# PCBmoteurs.net
KiCad netlist of a schematic drawn in EAGLE
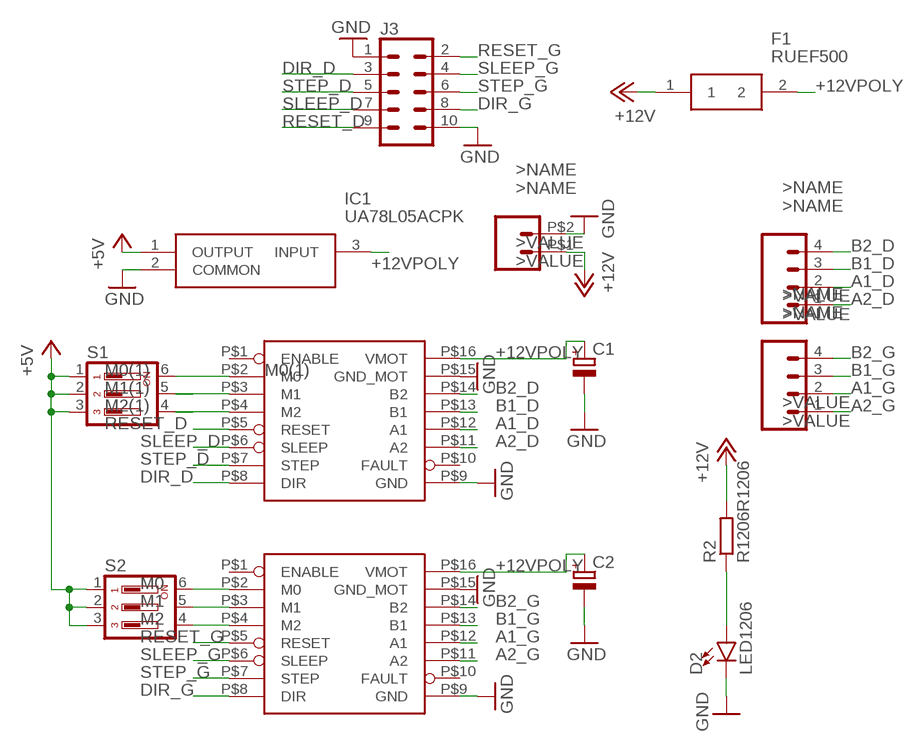
[diagram p0: schematic, sheet 1]

(export (version "E")
  (design (tool "Eeschema 10.0.6"))
  (components
    (comp (ref "C1")
      (value "CPOL-EUE3.5-8")
      (footprint "eagle-import:E3,5-8")
      (libsource (lib "eagle-import") (part "CPOL-EUE3.5-8"))
    )
    (comp (ref "C2")
      (value "CPOL-EUE3.5-8")
      (footprint "eagle-import:E3,5-8")
      (libsource (lib "eagle-import") (part "CPOL-EUE3.5-8"))
    )
    (comp (ref "D2")
      (value "LED1206")
      (footprint "eagle-import:1206")
      (libsource (lib "eagle-import") (part "LED1206"))
    )
    (comp (ref "F1")
      (value "RUEF500")
      (footprint "eagle-import:RUEF500")
      (fields (field (name "RS_PART_NUMBER") "5176843"))
      (libsource (lib "eagle-import") (part "RUEF500"))
    )
    (comp (ref "IC1")
      (value "UA78L05ACPK")
      (footprint "eagle-import:PK(R-PSSO-F3)")
      (fields (field (name "MOUSER_PART_NUMBER") "595-UA78L05ACPK"))
      (libsource (lib "eagle-import") (part "UA78L05ACPK"))
    )
    (comp (ref "J2")
      (value "CONN_027A-C")
      (footprint "eagle-import:NSK396-2C")
      (libsource (lib "eagle-import") (part "CONN_027A-C"))
    )
    (comp (ref "J3")
      (value "CONN_05X2SHD")
      (footprint "eagle-import:2X5-SHROUDED")
      (libsource (lib "eagle-import") (part "CONN_05X2SHD"))
    )
    (comp (ref "J4")
      (value "CONN_04POLAR")
      (footprint "eagle-import:MOLEX-1X4")
      (libsource (lib "eagle-import") (part "CONN_04POLAR"))
    )
    (comp (ref "J6")
      (value "CONN_04POLAR")
      (footprint "eagle-import:MOLEX-1X4")
      (libsource (lib "eagle-import") (part "CONN_04POLAR"))
    )
    (comp (ref "R2")
      (value "R1206R1206")
      (footprint "eagle-import:R1206")
      (libsource (lib "eagle-import") (part "R1206R1206"))
    )
    (comp (ref "S1")
      (value "DS03")
      (footprint "eagle-import:DS-03")
      (libsource (lib "eagle-import") (part "DS03"))
    )
    (comp (ref "S2")
      (value "DS03")
      (footprint "eagle-import:DS-03")
      (libsource (lib "eagle-import") (part "DS03"))
    )
    (comp (ref "U$1")
      (value "DRV8825")
      (footprint "eagle-import:DRIVER_CARRIER_POLOLU_16")
      (libsource (lib "eagle-import") (part "DRV8825"))
    )
    (comp (ref "U$2")
      (value "DRV8825")
      (footprint "eagle-import:DRIVER_CARRIER_POLOLU_16")
      (libsource (lib "eagle-import") (part "DRV8825"))
    )
  )
  (nets
    (net (code "1") (name "+5V") (class "Default")
      (node (ref "IC1") (pin "1") (pinfunction "OUTPUT_1") (pintype "bidirectional"))
      (node (ref "S1") (pin "1") (pinfunction "1_1") (pintype "passive"))
      (node (ref "S1") (pin "2") (pinfunction "2_2") (pintype "passive"))
      (node (ref "S1") (pin "3") (pinfunction "3_3") (pintype "passive"))
      (node (ref "S2") (pin "1") (pinfunction "1_1") (pintype "passive"))
      (node (ref "S2") (pin "2") (pinfunction "2_2") (pintype "passive"))
      (node (ref "S2") (pin "3") (pinfunction "3_3") (pintype "passive"))
    )
    (net (code "2") (name "+12V") (class "Default")
      (node (ref "F1") (pin "1") (pinfunction "1_1") (pintype "bidirectional"))
      (node (ref "J2") (pin "P$1") (pinfunction "1_P$1") (pintype "passive"))
      (node (ref "R2") (pin "2") (pinfunction "2_2") (pintype "passive"))
    )
    (net (code "3") (name "/+12VPOLY") (class "Default")
      (node (ref "C1") (pin "+") (pinfunction "+_+") (pintype "passive"))
      (node (ref "C2") (pin "+") (pinfunction "+_+") (pintype "passive"))
      (node (ref "F1") (pin "2") (pinfunction "2_2") (pintype "bidirectional"))
      (node (ref "IC1") (pin "3") (pinfunction "INPUT_3") (pintype "bidirectional"))
      (node (ref "U$1") (pin "P$16") (pinfunction "VMOT_P$16") (pintype "bidirectional"))
      (node (ref "U$2") (pin "P$16") (pinfunction "VMOT_P$16") (pintype "bidirectional"))
    )
    (net (code "4") (name "/A1_D") (class "Default")
      (node (ref "J4") (pin "2") (pinfunction "2_2") (pintype "passive"))
      (node (ref "U$1") (pin "P$12") (pinfunction "A1_P$12") (pintype "bidirectional"))
    )
    (net (code "5") (name "/A1_G") (class "Default")
      (node (ref "J6") (pin "2") (pinfunction "2_2") (pintype "passive"))
      (node (ref "U$2") (pin "P$12") (pinfunction "A1_P$12") (pintype "bidirectional"))
    )
    (net (code "6") (name "/A2_D") (class "Default")
      (node (ref "J4") (pin "1") (pinfunction "1_1") (pintype "passive"))
      (node (ref "U$1") (pin "P$11") (pinfunction "A2_P$11") (pintype "bidirectional"))
    )
    (net (code "7") (name "/A2_G") (class "Default")
      (node (ref "J6") (pin "1") (pinfunction "1_1") (pintype "passive"))
      (node (ref "U$2") (pin "P$11") (pinfunction "A2_P$11") (pintype "bidirectional"))
    )
    (net (code "8") (name "/B1_D") (class "Default")
      (node (ref "J4") (pin "3") (pinfunction "3_3") (pintype "passive"))
      (node (ref "U$1") (pin "P$13") (pinfunction "B1_P$13") (pintype "bidirectional"))
    )
    (net (code "9") (name "/B1_G") (class "Default")
      (node (ref "J6") (pin "3") (pinfunction "3_3") (pintype "passive"))
      (node (ref "U$2") (pin "P$13") (pinfunction "B1_P$13") (pintype "bidirectional"))
    )
    (net (code "10") (name "/B2_D") (class "Default")
      (node (ref "J4") (pin "4") (pinfunction "4_4") (pintype "passive"))
      (node (ref "U$1") (pin "P$14") (pinfunction "B2_P$14") (pintype "bidirectional"))
    )
    (net (code "11") (name "/B2_G") (class "Default")
      (node (ref "J6") (pin "4") (pinfunction "4_4") (pintype "passive"))
      (node (ref "U$2") (pin "P$14") (pinfunction "B2_P$14") (pintype "bidirectional"))
    )
    (net (code "12") (name "/DIR_D") (class "Default")
      (node (ref "J3") (pin "3") (pinfunction "3_3") (pintype "passive"))
      (node (ref "U$1") (pin "P$8") (pinfunction "DIR_P$8") (pintype "bidirectional"))
    )
    (net (code "13") (name "/DIR_G") (class "Default")
      (node (ref "J3") (pin "8") (pinfunction "8_8") (pintype "passive"))
      (node (ref "U$2") (pin "P$8") (pinfunction "DIR_P$8") (pintype "bidirectional"))
    )
    (net (code "14") (name "/M0") (class "Default")
      (node (ref "S2") (pin "6") (pinfunction "6_6") (pintype "passive"))
      (node (ref "U$2") (pin "P$2") (pinfunction "M0_P$2") (pintype "bidirectional"))
    )
    (net (code "15") (name "/M0(1)") (class "Default")
      (node (ref "S1") (pin "6") (pinfunction "6_6") (pintype "passive"))
      (node (ref "U$1") (pin "P$2") (pinfunction "M0_P$2") (pintype "bidirectional"))
    )
    (net (code "16") (name "/M1") (class "Default")
      (node (ref "S2") (pin "5") (pinfunction "5_5") (pintype "passive"))
      (node (ref "U$2") (pin "P$3") (pinfunction "M1_P$3") (pintype "bidirectional"))
    )
    (net (code "17") (name "/M1(1)") (class "Default")
      (node (ref "S1") (pin "5") (pinfunction "5_5") (pintype "passive"))
      (node (ref "U$1") (pin "P$3") (pinfunction "M1_P$3") (pintype "bidirectional"))
    )
    (net (code "18") (name "/M2") (class "Default")
      (node (ref "S2") (pin "4") (pinfunction "4_4") (pintype "passive"))
      (node (ref "U$2") (pin "P$4") (pinfunction "M2_P$4") (pintype "bidirectional"))
    )
    (net (code "19") (name "/M2(1)") (class "Default")
      (node (ref "S1") (pin "4") (pinfunction "4_4") (pintype "passive"))
      (node (ref "U$1") (pin "P$4") (pinfunction "M2_P$4") (pintype "bidirectional"))
    )
    (net (code "20") (name "/RESET_D") (class "Default")
      (node (ref "J3") (pin "9") (pinfunction "9_9") (pintype "passive"))
      (node (ref "U$1") (pin "P$5") (pinfunction "RESET_P$5") (pintype "bidirectional"))
    )
    (net (code "21") (name "/RESET_G") (class "Default")
      (node (ref "J3") (pin "2") (pinfunction "2_2") (pintype "passive"))
      (node (ref "U$2") (pin "P$5") (pinfunction "RESET_P$5") (pintype "bidirectional"))
    )
    (net (code "22") (name "/SLEEP_D") (class "Default")
      (node (ref "J3") (pin "7") (pinfunction "7_7") (pintype "passive"))
      (node (ref "U$1") (pin "P$6") (pinfunction "SLEEP_P$6") (pintype "bidirectional"))
    )
    (net (code "23") (name "/SLEEP_G") (class "Default")
      (node (ref "J3") (pin "4") (pinfunction "4_4") (pintype "passive"))
      (node (ref "U$2") (pin "P$6") (pinfunction "SLEEP_P$6") (pintype "bidirectional"))
    )
    (net (code "24") (name "/STEP_D") (class "Default")
      (node (ref "J3") (pin "5") (pinfunction "5_5") (pintype "passive"))
      (node (ref "U$1") (pin "P$7") (pinfunction "STEP_P$7") (pintype "bidirectional"))
    )
    (net (code "25") (name "/STEP_G") (class "Default")
      (node (ref "J3") (pin "6") (pinfunction "6_6") (pintype "passive"))
      (node (ref "U$2") (pin "P$7") (pinfunction "STEP_P$7") (pintype "bidirectional"))
    )
    (net (code "26") (name "GND") (class "Default")
      (node (ref "C1") (pin "-") (pinfunction "-_-") (pintype "passive"))
      (node (ref "C2") (pin "-") (pinfunction "-_-") (pintype "passive"))
      (node (ref "D2") (pin "C") (pinfunction "C_C") (pintype "passive"))
      (node (ref "IC1") (pin "2") (pinfunction "COMMON_2") (pintype "bidirectional"))
      (node (ref "J2") (pin "P$2") (pinfunction "2_P$2") (pintype "passive"))
      (node (ref "J3") (pin "1") (pinfunction "1_1") (pintype "passive"))
      (node (ref "J3") (pin "10") (pinfunction "10_10") (pintype "passive"))
      (node (ref "U$1") (pin "P$15") (pinfunction "GND_MOT_P$15") (pintype "bidirectional"))
      (node (ref "U$1") (pin "P$9") (pinfunction "GND_P$9") (pintype "bidirectional"))
      (node (ref "U$2") (pin "P$15") (pinfunction "GND_MOT_P$15") (pintype "bidirectional"))
      (node (ref "U$2") (pin "P$9") (pinfunction "GND_P$9") (pintype "bidirectional"))
    )
    (net (code "27") (name "Net-(D2-PadA)") (class "Default")
      (node (ref "D2") (pin "A") (pinfunction "A_A") (pintype "passive"))
      (node (ref "R2") (pin "1") (pinfunction "1_1") (pintype "passive"))
    )
    (net (code "28") (name "unconnected-(U$1-ENABLE-PadP$1)") (class "Default")
      (node (ref "U$1") (pin "P$1") (pinfunction "ENABLE_P$1") (pintype "bidirectional"))
    )
    (net (code "29") (name "unconnected-(U$1-FAULT-PadP$10)") (class "Default")
      (node (ref "U$1") (pin "P$10") (pinfunction "FAULT_P$10") (pintype "bidirectional"))
    )
    (net (code "30") (name "unconnected-(U$2-ENABLE-PadP$1)") (class "Default")
      (node (ref "U$2") (pin "P$1") (pinfunction "ENABLE_P$1") (pintype "bidirectional"))
    )
    (net (code "31") (name "unconnected-(U$2-FAULT-PadP$10)") (class "Default")
      (node (ref "U$2") (pin "P$10") (pinfunction "FAULT_P$10") (pintype "bidirectional"))
    )
  )
)
